# BMS_AFE_-_Communications.net
KiCad netlist of a schematic drawn in Altium Designer
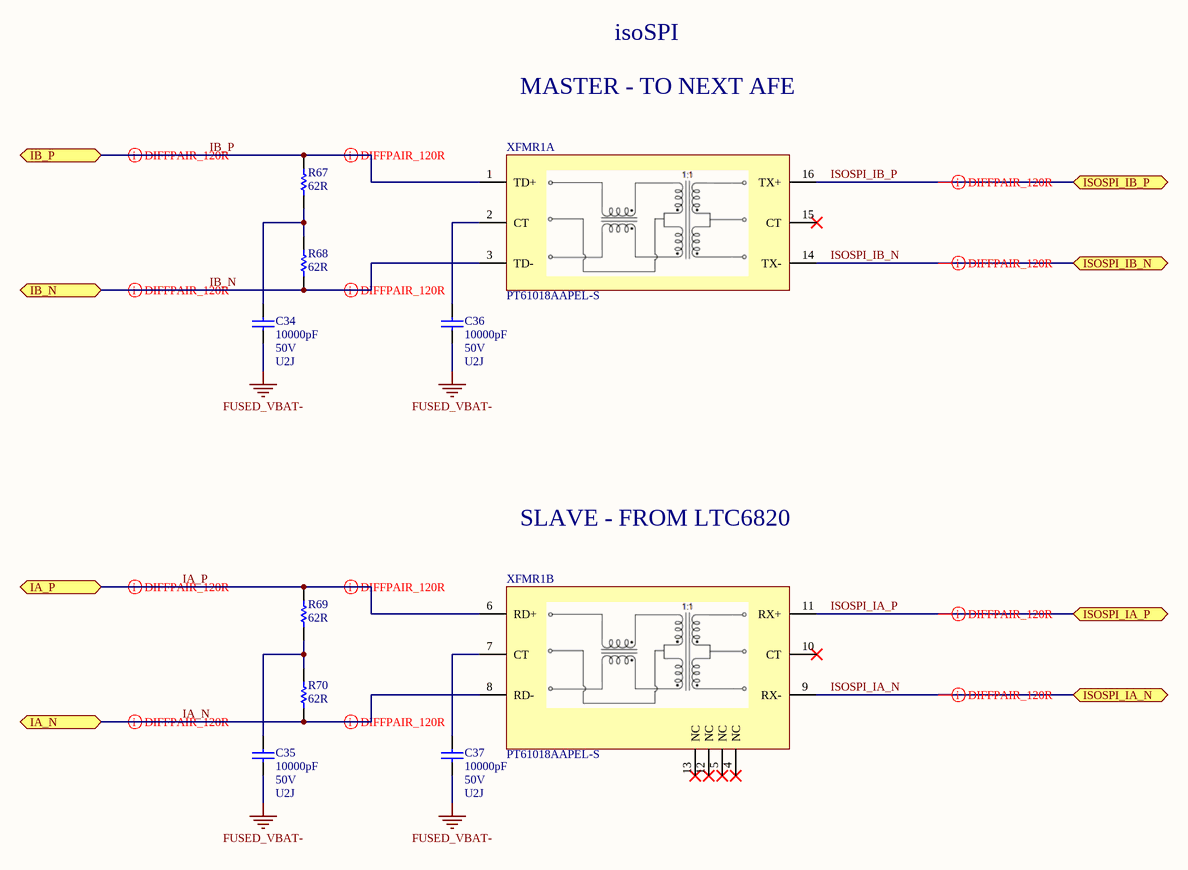
[diagram p0: BMS AFE - Communications.SchDoc]

(export (version "E")
  (design (tool "Eeschema 10.0.6"))
  (components
    (comp (ref "C34")
      (value "CAP CER 10nF 50V 5% X7R 0603")
      (footprint "CAP, 0603")
      (description "10000pF ±5% 50V Ceramic Capacitor U2J 0603 (1608 Metric)")
      (fields
        (field (name "TOLERANCE") "±5%")
        (field (name "CAPACITANCE") "10000pF")
        (field (name "VOLTAGE") "50V")
        (field (name "TEMPERATURE COEFFICIENT") "U2J")
      )
      (libsource (lib "Schematic Diagrams") (part "CAP CER 10nF 50V 5% X7R 0603"))
    )
    (comp (ref "C35")
      (value "CAP CER 10nF 50V 5% X7R 0603")
      (footprint "CAP, 0603")
      (description "10000pF ±5% 50V Ceramic Capacitor U2J 0603 (1608 Metric)")
      (fields
        (field (name "TOLERANCE") "±5%")
        (field (name "CAPACITANCE") "10000pF")
        (field (name "VOLTAGE") "50V")
        (field (name "TEMPERATURE COEFFICIENT") "U2J")
      )
      (libsource (lib "Schematic Diagrams") (part "CAP CER 10nF 50V 5% X7R 0603"))
    )
    (comp (ref "C36")
      (value "CAP CER 10nF 50V 5% X7R 0603")
      (footprint "CAP, 0603")
      (description "10000pF ±5% 50V Ceramic Capacitor U2J 0603 (1608 Metric)")
      (fields
        (field (name "TOLERANCE") "±5%")
        (field (name "CAPACITANCE") "10000pF")
        (field (name "VOLTAGE") "50V")
        (field (name "TEMPERATURE COEFFICIENT") "U2J")
      )
      (libsource (lib "Schematic Diagrams") (part "CAP CER 10nF 50V 5% X7R 0603"))
    )
    (comp (ref "C37")
      (value "CAP CER 10nF 50V 5% X7R 0603")
      (footprint "CAP, 0603")
      (description "10000pF ±5% 50V Ceramic Capacitor U2J 0603 (1608 Metric)")
      (fields
        (field (name "TOLERANCE") "±5%")
        (field (name "CAPACITANCE") "10000pF")
        (field (name "VOLTAGE") "50V")
        (field (name "TEMPERATURE COEFFICIENT") "U2J")
      )
      (libsource (lib "Schematic Diagrams") (part "CAP CER 10nF 50V 5% X7R 0603"))
    )
    (comp (ref "R67")
      (value "62R")
      (footprint "RES, 0603")
      (description "62 Ohms ±0.1% 0.1W, 1/10W Chip Resistor 0603 (1608 Metric) Automotive AEC-Q200 Thin Film")
      (fields
        (field (name "MANUFACTURER") "Panasonic Electronic Components")
        (field (name "MANUFACTURER PART NUMBER") "ERA-3AEB620V")
      )
      (libsource (lib "Schematic Diagrams") (part "RES 62 OHM 0.1% 1/10W 0603"))
    )
    (comp (ref "R68")
      (value "62R")
      (footprint "RES, 0603")
      (description "62 Ohms ±0.1% 0.1W, 1/10W Chip Resistor 0603 (1608 Metric) Automotive AEC-Q200 Thin Film")
      (fields
        (field (name "MANUFACTURER") "Panasonic Electronic Components")
        (field (name "MANUFACTURER PART NUMBER") "ERA-3AEB620V")
      )
      (libsource (lib "Schematic Diagrams") (part "RES 62 OHM 0.1% 1/10W 0603"))
    )
    (comp (ref "R69")
      (value "62R")
      (footprint "RES, 0603")
      (description "62 Ohms ±0.1% 0.1W, 1/10W Chip Resistor 0603 (1608 Metric) Automotive AEC-Q200 Thin Film")
      (fields
        (field (name "MANUFACTURER") "Panasonic Electronic Components")
        (field (name "MANUFACTURER PART NUMBER") "ERA-3AEB620V")
      )
      (libsource (lib "Schematic Diagrams") (part "RES 62 OHM 0.1% 1/10W 0603"))
    )
    (comp (ref "R70")
      (value "62R")
      (footprint "RES, 0603")
      (description "62 Ohms ±0.1% 0.1W, 1/10W Chip Resistor 0603 (1608 Metric) Automotive AEC-Q200 Thin Film")
      (fields
        (field (name "MANUFACTURER") "Panasonic Electronic Components")
        (field (name "MANUFACTURER PART NUMBER") "ERA-3AEB620V")
      )
      (libsource (lib "Schematic Diagrams") (part "RES 62 OHM 0.1% 1/10W 0603"))
    )
    (comp (ref "XFMR1")
      (value "IC PULSE XFMR 1CT:1CT 350UH SMD")
      (footprint "IC, PULSE XFMR 1CT:1CT 350UH SMD")
      (description "PULSE XFMR 1CT:1CT 350UH SMD")
      (fields (field (name "MANUFACTURER") "Bourns Inc.") (field (name "MFG_PN") "PT61018AAPEL-S"))
      (libsource (lib "Schematic Diagrams") (part "IC PULSE XFMR 1CT{colon}1CT 350UH SMD"))
    )
  )
  (nets
    (net (code "1") (name "/IA_N") (class "Default")
      (node (ref "R70") (pin "2") (pinfunction "2_2") (pintype "passive"))
      (node (ref "XFMR1") (pin "8") (pinfunction "RD-_8") (pintype "passive"))
    )
    (net (code "2") (name "/IA_P") (class "Default")
      (node (ref "R69") (pin "1") (pinfunction "1_1") (pintype "passive"))
      (node (ref "XFMR1") (pin "6") (pinfunction "RD+_6") (pintype "passive"))
    )
    (net (code "3") (name "/IB_N") (class "Default")
      (node (ref "R68") (pin "2") (pinfunction "2_2") (pintype "passive"))
      (node (ref "XFMR1") (pin "3") (pinfunction "TD-_3") (pintype "passive"))
    )
    (net (code "4") (name "/IB_P") (class "Default")
      (node (ref "R67") (pin "1") (pinfunction "1_1") (pintype "passive"))
      (node (ref "XFMR1") (pin "1") (pinfunction "TD+_1") (pintype "passive"))
    )
    (net (code "5") (name "/ISOSPI_IA_N") (class "Default")
      (node (ref "XFMR1") (pin "9") (pinfunction "RX-_9") (pintype "passive"))
    )
    (net (code "6") (name "/ISOSPI_IA_P") (class "Default")
      (node (ref "XFMR1") (pin "11") (pinfunction "RX+_11") (pintype "passive"))
    )
    (net (code "7") (name "/ISOSPI_IB_N") (class "Default")
      (node (ref "XFMR1") (pin "14") (pinfunction "TX-_14") (pintype "passive"))
    )
    (net (code "8") (name "/ISOSPI_IB_P") (class "Default")
      (node (ref "XFMR1") (pin "16") (pinfunction "TX+_16") (pintype "passive"))
    )
    (net (code "9") (name "FUSED_VBAT-") (class "Default")
      (node (ref "C34") (pin "2") (pinfunction "2_2") (pintype "passive"))
      (node (ref "C35") (pin "2") (pinfunction "2_2") (pintype "passive"))
      (node (ref "C36") (pin "2") (pinfunction "2_2") (pintype "passive"))
      (node (ref "C37") (pin "2") (pinfunction "2_2") (pintype "passive"))
    )
    (net (code "10") (name "Net-(C34-Pad1)") (class "Default")
      (node (ref "C34") (pin "1") (pinfunction "1_1") (pintype "passive"))
      (node (ref "R67") (pin "2") (pinfunction "2_2") (pintype "passive"))
      (node (ref "R68") (pin "1") (pinfunction "1_1") (pintype "passive"))
    )
    (net (code "11") (name "Net-(C35-Pad1)") (class "Default")
      (node (ref "C35") (pin "1") (pinfunction "1_1") (pintype "passive"))
      (node (ref "R69") (pin "2") (pinfunction "2_2") (pintype "passive"))
      (node (ref "R70") (pin "1") (pinfunction "1_1") (pintype "passive"))
    )
    (net (code "12") (name "Net-(C36-Pad1)") (class "Default")
      (node (ref "C36") (pin "1") (pinfunction "1_1") (pintype "passive"))
      (node (ref "XFMR1") (pin "2") (pinfunction "CT_2") (pintype "passive"))
    )
    (net (code "13") (name "Net-(C37-Pad1)") (class "Default")
      (node (ref "C37") (pin "1") (pinfunction "1_1") (pintype "passive"))
      (node (ref "XFMR1") (pin "7") (pinfunction "CT_7") (pintype "passive"))
    )
    (net (code "14") (name "unconnected-(XFMR1A-CT-Pad15)") (class "Default")
      (node (ref "XFMR1") (pin "15") (pinfunction "CT_15") (pintype "passive+no_connect"))
    )
    (net (code "15") (name "unconnected-(XFMR1B-CT-Pad10)") (class "Default")
      (node (ref "XFMR1") (pin "10") (pinfunction "CT_10") (pintype "passive+no_connect"))
    )
    (net (code "16") (name "unconnected-(XFMR1B-NC-Pad4)") (class "Default")
      (node (ref "XFMR1") (pin "4") (pinfunction "NC_4") (pintype "passive+no_connect"))
    )
    (net (code "17") (name "unconnected-(XFMR1B-NC-Pad5)") (class "Default")
      (node (ref "XFMR1") (pin "5") (pinfunction "NC_5") (pintype "passive+no_connect"))
    )
    (net (code "18") (name "unconnected-(XFMR1B-NC-Pad12)") (class "Default")
      (node (ref "XFMR1") (pin "12") (pinfunction "NC_12") (pintype "passive+no_connect"))
    )
    (net (code "19") (name "unconnected-(XFMR1B-NC-Pad13)") (class "Default")
      (node (ref "XFMR1") (pin "13") (pinfunction "NC_13") (pintype "passive+no_connect"))
    )
  )
)
